# haptic_ring.net
KiCad netlist of a schematic drawn in Altium Designer
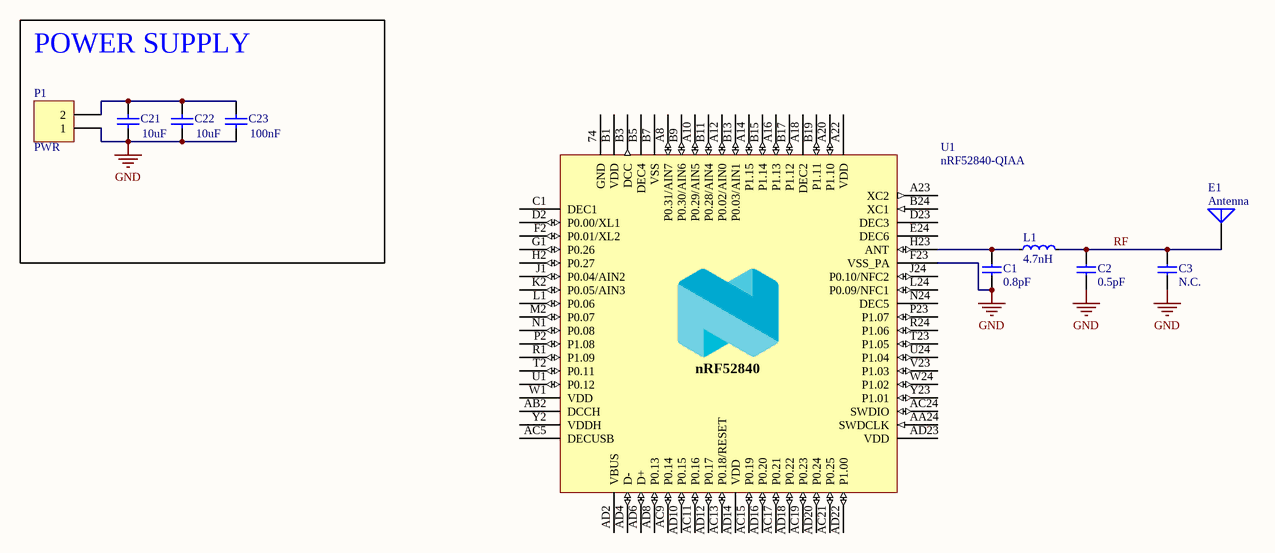
[diagram p0: haptic_ring.SchDoc]

(export (version "E")
  (design (tool "Eeschema 10.0.6"))
  (components
    (comp (ref "C1")
      (value "0.8pF")
      (footprint "C_1005")
      (description "Capacitor, NP0, ±10%")
      (fields (field (name "PART NUMBER") "C0402-0.8p"))
      (libsource (lib "AltiumLib") (part "CAP"))
    )
    (comp (ref "C2")
      (value "0.5pF")
      (footprint "C_1005")
      (description "Capacitor, NP0, ±10%")
      (fields (field (name "PART NUMBER") "C0402-0.5p"))
      (libsource (lib "AltiumLib") (part "CAP"))
    )
    (comp (ref "C3")
      (value "N.C.")
      (footprint "C_1005")
      (description "Not mounted")
      (fields (field (name "PART NUMBER") "C0402-N.C."))
      (libsource (lib "AltiumLib") (part "CAP"))
    )
    (comp (ref "C21")
      (value "10uF")
      (footprint "C_0402")
      (description "Capacitor (Semiconductor SIM Model)")
      (fields (field (name "Comment") "Cap Semi") (field (name "PUBLISHER") "Altium Limited"))
      (libsource (lib "Miscellaneous Devices") (part "Cap Semi"))
    )
    (comp (ref "C22")
      (value "10uF")
      (footprint "C_0402")
      (description "Capacitor (Semiconductor SIM Model)")
      (fields (field (name "Comment") "Cap Semi") (field (name "PUBLISHER") "Altium Limited"))
      (libsource (lib "Miscellaneous Devices") (part "Cap Semi"))
    )
    (comp (ref "C23")
      (value "100nF")
      (footprint "C_0402")
      (description "Capacitor (Semiconductor SIM Model)")
      (fields (field (name "Comment") "Cap Semi") (field (name "PUBLISHER") "Altium Limited"))
      (libsource (lib "Miscellaneous Devices") (part "Cap Semi"))
    )
    (comp (ref "E1")
      (value "Antenna")
      (footprint "2450AT18B100")
      (description "Generic Antenna")
      (fields (field (name "PUBLISHER") "Altium Limited"))
      (libsource (lib "Miscellaneous Devices") (part "Antenna"))
    )
    (comp (ref "L1")
      (value "4.7nH")
      (footprint "L_1005")
      (description "High frequency chip inductor ±5%")
      (fields (field (name "PART NUMBER") "L0402-4n7"))
      (libsource (lib "AltiumLib") (part "IND"))
    )
    (comp (ref "P1")
      (value "PWR")
      (footprint "HDR1X2")
      (description "Header, 2-Pin")
      (fields (field (name "PUBLISHER") "Altium Limited"))
      (libsource (lib "Miscellaneous Connectors") (part "Header 2"))
    )
    (comp (ref "U1")
      (value "nRF52840-QIAA")
      (footprint "AQFN50P700X700X85_HS-74N")
      (description "Multi-protocol Bluetooth Low Energy, IEEE 802.15.4, ANT and 2.4GHz proprietary system-on-chip")
      (libsource (lib "My_lib") (part "nRF52840-QIAA"))
    )
  )
  (nets
    (net (code "1") (name "/RF") (class "Default")
      (node (ref "C2") (pin "2") (pinfunction "2_2") (pintype "passive"))
      (node (ref "C3") (pin "1") (pinfunction "1_1") (pintype "passive"))
      (node (ref "E1") (pin "1") (pinfunction "A_1") (pintype "passive"))
      (node (ref "L1") (pin "2") (pinfunction "2_2") (pintype "passive"))
    )
    (net (code "2") (name "GND") (class "Default")
      (node (ref "C1") (pin "1") (pinfunction "1_1") (pintype "passive"))
      (node (ref "C2") (pin "1") (pinfunction "1_1") (pintype "passive"))
      (node (ref "C21") (pin "1") (pinfunction "1_1") (pintype "passive"))
      (node (ref "C22") (pin "1") (pinfunction "1_1") (pintype "passive"))
      (node (ref "C23") (pin "1") (pinfunction "1_1") (pintype "passive"))
      (node (ref "C3") (pin "2") (pinfunction "2_2") (pintype "passive"))
      (node (ref "P1") (pin "1") (pinfunction "1_1") (pintype "passive"))
      (node (ref "U1") (pin "F23") (pinfunction "VSS_PA_F23") (pintype "power_in"))
    )
    (net (code "3") (name "Net-(C21-Pad2)") (class "Default")
      (node (ref "C21") (pin "2") (pinfunction "2_2") (pintype "passive"))
      (node (ref "C22") (pin "2") (pinfunction "2_2") (pintype "passive"))
      (node (ref "C23") (pin "2") (pinfunction "2_2") (pintype "passive"))
      (node (ref "P1") (pin "2") (pinfunction "2_2") (pintype "passive"))
    )
    (net (code "4") (name "Net-(U1-ANT)") (class "Default")
      (node (ref "C1") (pin "2") (pinfunction "2_2") (pintype "passive"))
      (node (ref "L1") (pin "1") (pinfunction "1_1") (pintype "passive"))
      (node (ref "U1") (pin "H23") (pinfunction "ANT_H23") (pintype "bidirectional"))
    )
    (net (code "5") (name "unconnected-(U1-D+-PadAD6)") (class "Default")
      (node (ref "U1") (pin "AD6") (pinfunction "D+_AD6") (pintype "bidirectional"))
    )
    (net (code "6") (name "unconnected-(U1-D--PadAD4)") (class "Default")
      (node (ref "U1") (pin "AD4") (pinfunction "D-_AD4") (pintype "bidirectional"))
    )
    (net (code "7") (name "unconnected-(U1-DCC-PadB3)") (class "Default")
      (node (ref "U1") (pin "B3") (pinfunction "DCC_B3") (pintype "output"))
    )
    (net (code "8") (name "unconnected-(U1-DCCH-PadAB2)") (class "Default")
      (node (ref "U1") (pin "AB2") (pinfunction "DCCH_AB2") (pintype "power_in"))
    )
    (net (code "9") (name "unconnected-(U1-DEC1-PadC1)") (class "Default")
      (node (ref "U1") (pin "C1") (pinfunction "DEC1_C1") (pintype "power_in"))
    )
    (net (code "10") (name "unconnected-(U1-DEC2-PadA18)") (class "Default")
      (node (ref "U1") (pin "A18") (pinfunction "DEC2_A18") (pintype "power_in"))
    )
    (net (code "11") (name "unconnected-(U1-DEC3-PadD23)") (class "Default")
      (node (ref "U1") (pin "D23") (pinfunction "DEC3_D23") (pintype "power_in"))
    )
    (net (code "12") (name "unconnected-(U1-DEC4-PadB5)") (class "Default")
      (node (ref "U1") (pin "B5") (pinfunction "DEC4_B5") (pintype "power_in"))
    )
    (net (code "13") (name "unconnected-(U1-DEC5-PadN24)") (class "Default")
      (node (ref "U1") (pin "N24") (pinfunction "DEC5_N24") (pintype "power_in"))
    )
    (net (code "14") (name "unconnected-(U1-DEC6-PadE24)") (class "Default")
      (node (ref "U1") (pin "E24") (pinfunction "DEC6_E24") (pintype "power_in"))
    )
    (net (code "15") (name "unconnected-(U1-DECUSB-PadAC5)") (class "Default")
      (node (ref "U1") (pin "AC5") (pinfunction "DECUSB_AC5") (pintype "power_in"))
    )
    (net (code "16") (name "unconnected-(U1-GND-Pad74)") (class "Default")
      (node (ref "U1") (pin "74") (pinfunction "GND_74") (pintype "power_in"))
    )
    (net (code "17") (name "unconnected-(U1-P0.00{slash}XL1-PadD2)") (class "Default")
      (node (ref "U1") (pin "D2") (pinfunction "P0.00/XL1_D2") (pintype "bidirectional"))
    )
    (net (code "18") (name "unconnected-(U1-P0.01{slash}XL2-PadF2)") (class "Default")
      (node (ref "U1") (pin "F2") (pinfunction "P0.01/XL2_F2") (pintype "bidirectional"))
    )
    (net (code "19") (name "unconnected-(U1-P0.02{slash}AIN0-PadA12)") (class "Default")
      (node (ref "U1") (pin "A12") (pinfunction "P0.02/AIN0_A12") (pintype "bidirectional"))
    )
    (net (code "20") (name "unconnected-(U1-P0.03{slash}AIN1-PadB13)") (class "Default")
      (node (ref "U1") (pin "B13") (pinfunction "P0.03/AIN1_B13") (pintype "bidirectional"))
    )
    (net (code "21") (name "unconnected-(U1-P0.04{slash}AIN2-PadJ1)") (class "Default")
      (node (ref "U1") (pin "J1") (pinfunction "P0.04/AIN2_J1") (pintype "bidirectional"))
    )
    (net (code "22") (name "unconnected-(U1-P0.05{slash}AIN3-PadK2)") (class "Default")
      (node (ref "U1") (pin "K2") (pinfunction "P0.05/AIN3_K2") (pintype "bidirectional"))
    )
    (net (code "23") (name "unconnected-(U1-P0.06-PadL1)") (class "Default")
      (node (ref "U1") (pin "L1") (pinfunction "P0.06_L1") (pintype "bidirectional"))
    )
    (net (code "24") (name "unconnected-(U1-P0.07-PadM2)") (class "Default")
      (node (ref "U1") (pin "M2") (pinfunction "P0.07_M2") (pintype "bidirectional"))
    )
    (net (code "25") (name "unconnected-(U1-P0.08-PadN1)") (class "Default")
      (node (ref "U1") (pin "N1") (pinfunction "P0.08_N1") (pintype "bidirectional"))
    )
    (net (code "26") (name "unconnected-(U1-P0.09{slash}NFC1-PadL24)") (class "Default")
      (node (ref "U1") (pin "L24") (pinfunction "P0.09/NFC1_L24") (pintype "bidirectional"))
    )
    (net (code "27") (name "unconnected-(U1-P0.10{slash}NFC2-PadJ24)") (class "Default")
      (node (ref "U1") (pin "J24") (pinfunction "P0.10/NFC2_J24") (pintype "bidirectional"))
    )
    (net (code "28") (name "unconnected-(U1-P0.11-PadT2)") (class "Default")
      (node (ref "U1") (pin "T2") (pinfunction "P0.11_T2") (pintype "bidirectional"))
    )
    (net (code "29") (name "unconnected-(U1-P0.12-PadU1)") (class "Default")
      (node (ref "U1") (pin "U1") (pinfunction "P0.12_U1") (pintype "bidirectional"))
    )
    (net (code "30") (name "unconnected-(U1-P0.13-PadAD8)") (class "Default")
      (node (ref "U1") (pin "AD8") (pinfunction "P0.13_AD8") (pintype "bidirectional"))
    )
    (net (code "31") (name "unconnected-(U1-P0.14-PadAC9)") (class "Default")
      (node (ref "U1") (pin "AC9") (pinfunction "P0.14_AC9") (pintype "bidirectional"))
    )
    (net (code "32") (name "unconnected-(U1-P0.15-PadAD10)") (class "Default")
      (node (ref "U1") (pin "AD10") (pinfunction "P0.15_AD10") (pintype "bidirectional"))
    )
    (net (code "33") (name "unconnected-(U1-P0.16-PadAC11)") (class "Default")
      (node (ref "U1") (pin "AC11") (pinfunction "P0.16_AC11") (pintype "bidirectional"))
    )
    (net (code "34") (name "unconnected-(U1-P0.17-PadAD12)") (class "Default")
      (node (ref "U1") (pin "AD12") (pinfunction "P0.17_AD12") (pintype "bidirectional"))
    )
    (net (code "35") (name "unconnected-(U1-P0.18{slash}RESET-PadAC13)") (class "Default")
      (node (ref "U1") (pin "AC13") (pinfunction "P0.18/RESET_AC13") (pintype "bidirectional"))
    )
    (net (code "36") (name "unconnected-(U1-P0.19-PadAC15)") (class "Default")
      (node (ref "U1") (pin "AC15") (pinfunction "P0.19_AC15") (pintype "bidirectional"))
    )
    (net (code "37") (name "unconnected-(U1-P0.20-PadAD16)") (class "Default")
      (node (ref "U1") (pin "AD16") (pinfunction "P0.20_AD16") (pintype "bidirectional"))
    )
    (net (code "38") (name "unconnected-(U1-P0.21-PadAC17)") (class "Default")
      (node (ref "U1") (pin "AC17") (pinfunction "P0.21_AC17") (pintype "bidirectional"))
    )
    (net (code "39") (name "unconnected-(U1-P0.22-PadAD18)") (class "Default")
      (node (ref "U1") (pin "AD18") (pinfunction "P0.22_AD18") (pintype "bidirectional"))
    )
    (net (code "40") (name "unconnected-(U1-P0.23-PadAC19)") (class "Default")
      (node (ref "U1") (pin "AC19") (pinfunction "P0.23_AC19") (pintype "bidirectional"))
    )
    (net (code "41") (name "unconnected-(U1-P0.24-PadAD20)") (class "Default")
      (node (ref "U1") (pin "AD20") (pinfunction "P0.24_AD20") (pintype "bidirectional"))
    )
    (net (code "42") (name "unconnected-(U1-P0.25-PadAC21)") (class "Default")
      (node (ref "U1") (pin "AC21") (pinfunction "P0.25_AC21") (pintype "bidirectional"))
    )
    (net (code "43") (name "unconnected-(U1-P0.26-PadG1)") (class "Default")
      (node (ref "U1") (pin "G1") (pinfunction "P0.26_G1") (pintype "bidirectional"))
    )
    (net (code "44") (name "unconnected-(U1-P0.27-PadH2)") (class "Default")
      (node (ref "U1") (pin "H2") (pinfunction "P0.27_H2") (pintype "bidirectional"))
    )
    (net (code "45") (name "unconnected-(U1-P0.28{slash}AIN4-PadB11)") (class "Default")
      (node (ref "U1") (pin "B11") (pinfunction "P0.28/AIN4_B11") (pintype "bidirectional"))
    )
    (net (code "46") (name "unconnected-(U1-P0.29{slash}AIN5-PadA10)") (class "Default")
      (node (ref "U1") (pin "A10") (pinfunction "P0.29/AIN5_A10") (pintype "bidirectional"))
    )
    (net (code "47") (name "unconnected-(U1-P0.30{slash}AIN6-PadB9)") (class "Default")
      (node (ref "U1") (pin "B9") (pinfunction "P0.30/AIN6_B9") (pintype "bidirectional"))
    )
    (net (code "48") (name "unconnected-(U1-P0.31{slash}AIN7-PadA8)") (class "Default")
      (node (ref "U1") (pin "A8") (pinfunction "P0.31/AIN7_A8") (pintype "bidirectional"))
    )
    (net (code "49") (name "unconnected-(U1-P1.00-PadAD22)") (class "Default")
      (node (ref "U1") (pin "AD22") (pinfunction "P1.00_AD22") (pintype "bidirectional"))
    )
    (net (code "50") (name "unconnected-(U1-P1.01-PadY23)") (class "Default")
      (node (ref "U1") (pin "Y23") (pinfunction "P1.01_Y23") (pintype "bidirectional"))
    )
    (net (code "51") (name "unconnected-(U1-P1.02-PadW24)") (class "Default")
      (node (ref "U1") (pin "W24") (pinfunction "P1.02_W24") (pintype "bidirectional"))
    )
    (net (code "52") (name "unconnected-(U1-P1.03-PadV23)") (class "Default")
      (node (ref "U1") (pin "V23") (pinfunction "P1.03_V23") (pintype "bidirectional"))
    )
    (net (code "53") (name "unconnected-(U1-P1.04-PadU24)") (class "Default")
      (node (ref "U1") (pin "U24") (pinfunction "P1.04_U24") (pintype "bidirectional"))
    )
    (net (code "54") (name "unconnected-(U1-P1.05-PadT23)") (class "Default")
      (node (ref "U1") (pin "T23") (pinfunction "P1.05_T23") (pintype "bidirectional"))
    )
    (net (code "55") (name "unconnected-(U1-P1.06-PadR24)") (class "Default")
      (node (ref "U1") (pin "R24") (pinfunction "P1.06_R24") (pintype "bidirectional"))
    )
    (net (code "56") (name "unconnected-(U1-P1.07-PadP23)") (class "Default")
      (node (ref "U1") (pin "P23") (pinfunction "P1.07_P23") (pintype "bidirectional"))
    )
    (net (code "57") (name "unconnected-(U1-P1.08-PadP2)") (class "Default")
      (node (ref "U1") (pin "P2") (pinfunction "P1.08_P2") (pintype "bidirectional"))
    )
    (net (code "58") (name "unconnected-(U1-P1.09-PadR1)") (class "Default")
      (node (ref "U1") (pin "R1") (pinfunction "P1.09_R1") (pintype "bidirectional"))
    )
    (net (code "59") (name "unconnected-(U1-P1.10-PadA20)") (class "Default")
      (node (ref "U1") (pin "A20") (pinfunction "P1.10_A20") (pintype "bidirectional"))
    )
    (net (code "60") (name "unconnected-(U1-P1.11-PadB19)") (class "Default")
      (node (ref "U1") (pin "B19") (pinfunction "P1.11_B19") (pintype "bidirectional"))
    )
    (net (code "61") (name "unconnected-(U1-P1.12-PadB17)") (class "Default")
      (node (ref "U1") (pin "B17") (pinfunction "P1.12_B17") (pintype "bidirectional"))
    )
    (net (code "62") (name "unconnected-(U1-P1.13-PadA16)") (class "Default")
      (node (ref "U1") (pin "A16") (pinfunction "P1.13_A16") (pintype "bidirectional"))
    )
    (net (code "63") (name "unconnected-(U1-P1.14-PadB15)") (class "Default")
      (node (ref "U1") (pin "B15") (pinfunction "P1.14_B15") (pintype "bidirectional"))
    )
    (net (code "64") (name "unconnected-(U1-P1.15-PadA14)") (class "Default")
      (node (ref "U1") (pin "A14") (pinfunction "P1.15_A14") (pintype "bidirectional"))
    )
    (net (code "65") (name "unconnected-(U1-SWDCLK-PadAA24)") (class "Default")
      (node (ref "U1") (pin "AA24") (pinfunction "SWDCLK_AA24") (pintype "input"))
    )
    (net (code "66") (name "unconnected-(U1-SWDIO-PadAC24)") (class "Default")
      (node (ref "U1") (pin "AC24") (pinfunction "SWDIO_AC24") (pintype "bidirectional"))
    )
    (net (code "67") (name "unconnected-(U1-VBUS-PadAD2)") (class "Default")
      (node (ref "U1") (pin "AD2") (pinfunction "VBUS_AD2") (pintype "power_in"))
    )
    (net (code "68") (name "unconnected-(U1-VDD-PadA22)") (class "Default")
      (node (ref "U1") (pin "A22") (pinfunction "VDD_A22") (pintype "power_in"))
    )
    (net (code "69") (name "unconnected-(U1-VDD-PadAD14)") (class "Default")
      (node (ref "U1") (pin "AD14") (pinfunction "VDD_AD14") (pintype "power_in"))
    )
    (net (code "70") (name "unconnected-(U1-VDD-PadAD23)") (class "Default")
      (node (ref "U1") (pin "AD23") (pinfunction "VDD_AD23") (pintype "power_in"))
    )
    (net (code "71") (name "unconnected-(U1-VDD-PadB1)") (class "Default")
      (node (ref "U1") (pin "B1") (pinfunction "VDD_B1") (pintype "power_in"))
    )
    (net (code "72") (name "unconnected-(U1-VDD-PadW1)") (class "Default")
      (node (ref "U1") (pin "W1") (pinfunction "VDD_W1") (pintype "power_in"))
    )
    (net (code "73") (name "unconnected-(U1-VDDH-PadY2)") (class "Default")
      (node (ref "U1") (pin "Y2") (pinfunction "VDDH_Y2") (pintype "power_in"))
    )
    (net (code "74") (name "unconnected-(U1-VSS-PadB7)") (class "Default")
      (node (ref "U1") (pin "B7") (pinfunction "VSS_B7") (pintype "power_in"))
    )
    (net (code "75") (name "unconnected-(U1-XC1-PadB24)") (class "Default")
      (node (ref "U1") (pin "B24") (pinfunction "XC1_B24") (pintype "input"))
    )
    (net (code "76") (name "unconnected-(U1-XC2-PadA23)") (class "Default")
      (node (ref "U1") (pin "A23") (pinfunction "XC2_A23") (pintype "output"))
    )
  )
)
